# SMARC_Pinout-1.net
KiCad netlist of a schematic drawn in Altium Designer
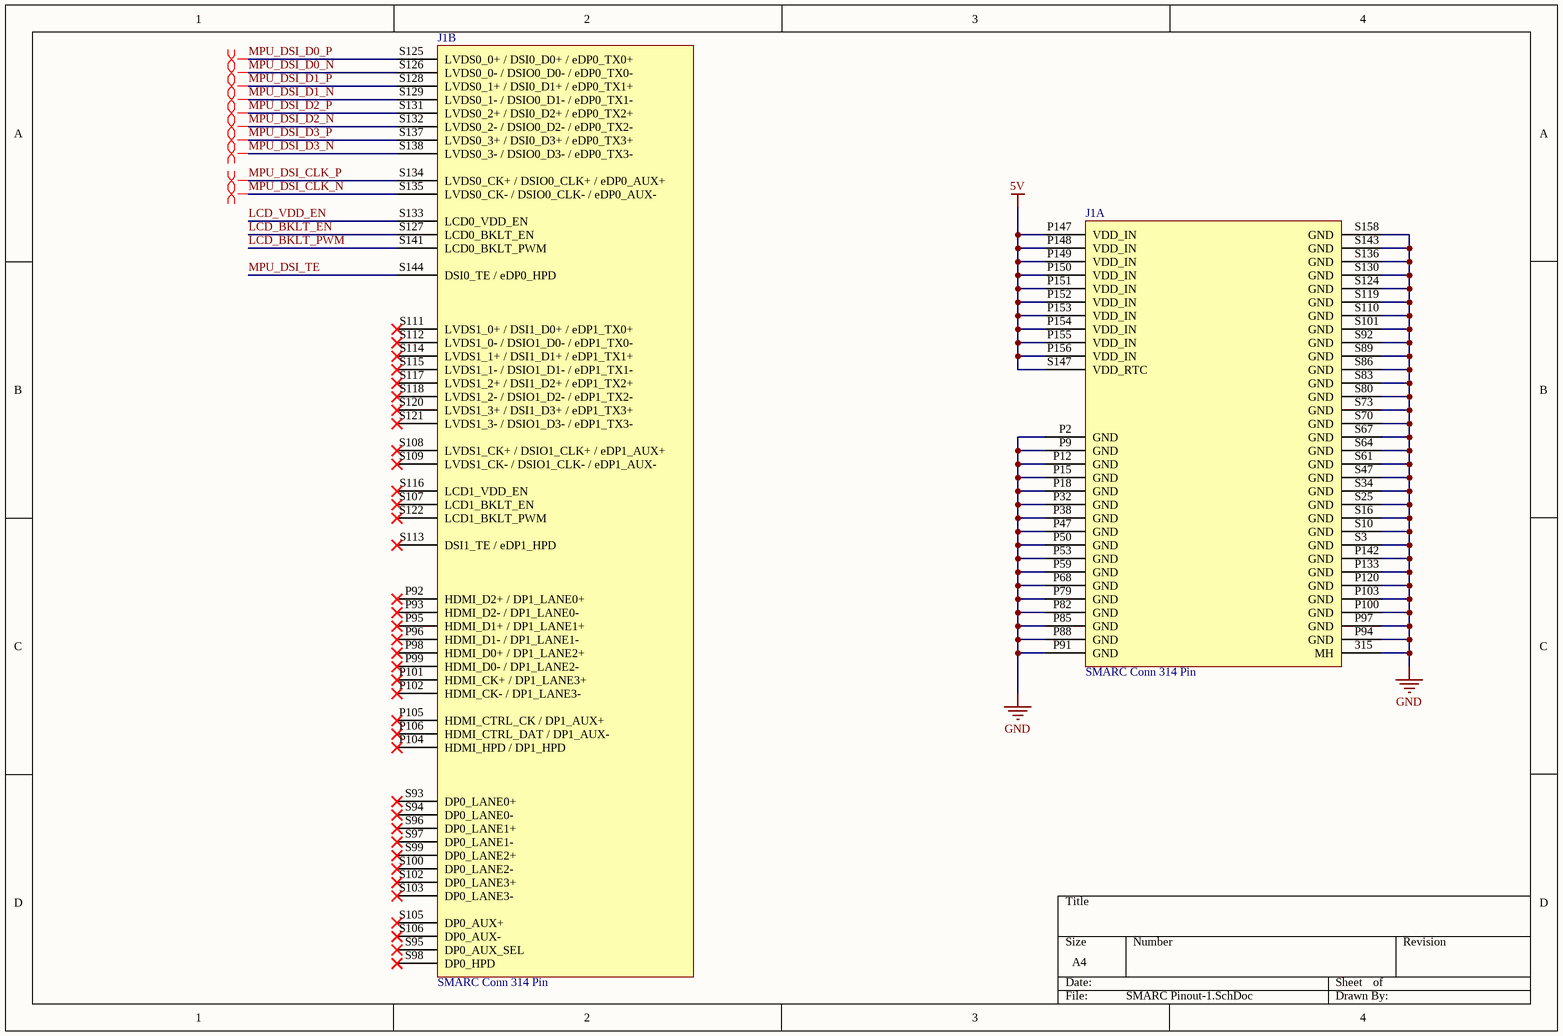
[diagram p0: SMARC Pinout-1.SchDoc]

(export (version "E")
  (design (tool "Eeschema 10.0.6"))
  (components
    (comp (ref "J1")
      (value "SMARC Conn 314 Pin")
      (footprint "SMARC Conn 314 Pin")
      (libsource (lib "Master") (part "SMARC Conn 314 Pin"))
    )
  )
  (nets
    (net (code "1") (name "/LCD_BKLT_EN") (class "Default")
      (node (ref "J1") (pin "S127") (pinfunction "LCD0_BKLT_EN_S127") (pintype "passive"))
    )
    (net (code "2") (name "/LCD_BKLT_PWM") (class "Default")
      (node (ref "J1") (pin "S141") (pinfunction "LCD0_BKLT_PWM_S141") (pintype "passive"))
    )
    (net (code "3") (name "/LCD_VDD_EN") (class "Default")
      (node (ref "J1") (pin "S133") (pinfunction "LCD0_VDD_EN_S133") (pintype "passive"))
    )
    (net (code "4") (name "/MPU_DSI_CLK_N") (class "Default")
      (node (ref "J1") (pin "S135") (pinfunction "LVDS0_CK-_/_DSIO0_CLK-_/_eDP0_AUX-_S135") (pintype "passive"))
    )
    (net (code "5") (name "/MPU_DSI_CLK_P") (class "Default")
      (node (ref "J1") (pin "S134") (pinfunction "LVDS0_CK+_/_DSIO0_CLK+_/_eDP0_AUX+_S134") (pintype "passive"))
    )
    (net (code "6") (name "/MPU_DSI_D0_N") (class "Default")
      (node (ref "J1") (pin "S126") (pinfunction "LVDS0_0-_/_DSIO0_D0-_/_eDP0_TX0-_S126") (pintype "passive"))
    )
    (net (code "7") (name "/MPU_DSI_D0_P") (class "Default")
      (node (ref "J1") (pin "S125") (pinfunction "LVDS0_0+_/_DSI0_D0+_/_eDP0_TX0+_S125") (pintype "passive"))
    )
    (net (code "8") (name "/MPU_DSI_D1_N") (class "Default")
      (node (ref "J1") (pin "S129") (pinfunction "LVDS0_1-_/_DSIO0_D1-_/_eDP0_TX1-_S129") (pintype "passive"))
    )
    (net (code "9") (name "/MPU_DSI_D1_P") (class "Default")
      (node (ref "J1") (pin "S128") (pinfunction "LVDS0_1+_/_DSI0_D1+_/_eDP0_TX1+_S128") (pintype "passive"))
    )
    (net (code "10") (name "/MPU_DSI_D2_N") (class "Default")
      (node (ref "J1") (pin "S132") (pinfunction "LVDS0_2-_/_DSIO0_D2-_/_eDP0_TX2-_S132") (pintype "passive"))
    )
    (net (code "11") (name "/MPU_DSI_D2_P") (class "Default")
      (node (ref "J1") (pin "S131") (pinfunction "LVDS0_2+_/_DSI0_D2+_/_eDP0_TX2+_S131") (pintype "passive"))
    )
    (net (code "12") (name "/MPU_DSI_D3_N") (class "Default")
      (node (ref "J1") (pin "S138") (pinfunction "LVDS0_3-_/_DSIO0_D3-_/_eDP0_TX3-_S138") (pintype "passive"))
    )
    (net (code "13") (name "/MPU_DSI_D3_P") (class "Default")
      (node (ref "J1") (pin "S137") (pinfunction "LVDS0_3+_/_DSI0_D3+_/_eDP0_TX3+_S137") (pintype "passive"))
    )
    (net (code "14") (name "/MPU_DSI_TE") (class "Default")
      (node (ref "J1") (pin "S144") (pinfunction "DSI0_TE_/_eDP0_HPD_S144") (pintype "passive"))
    )
    (net (code "15") (name "5V") (class "Default")
      (node (ref "J1") (pin "P147") (pinfunction "VDD_IN_P147") (pintype "passive"))
      (node (ref "J1") (pin "P148") (pinfunction "VDD_IN_P148") (pintype "passive"))
      (node (ref "J1") (pin "P149") (pinfunction "VDD_IN_P149") (pintype "passive"))
      (node (ref "J1") (pin "P150") (pinfunction "VDD_IN_P150") (pintype "passive"))
      (node (ref "J1") (pin "P151") (pinfunction "VDD_IN_P151") (pintype "passive"))
      (node (ref "J1") (pin "P152") (pinfunction "VDD_IN_P152") (pintype "passive"))
      (node (ref "J1") (pin "P153") (pinfunction "VDD_IN_P153") (pintype "passive"))
      (node (ref "J1") (pin "P154") (pinfunction "VDD_IN_P154") (pintype "passive"))
      (node (ref "J1") (pin "P155") (pinfunction "VDD_IN_P155") (pintype "passive"))
      (node (ref "J1") (pin "P156") (pinfunction "VDD_IN_P156") (pintype "passive"))
      (node (ref "J1") (pin "S147") (pinfunction "VDD_RTC_S147") (pintype "passive"))
    )
    (net (code "16") (name "GND") (class "Default")
      (node (ref "J1") (pin "315") (pinfunction "MH_315") (pintype "passive"))
      (node (ref "J1") (pin "P100") (pinfunction "GND_P100") (pintype "passive"))
      (node (ref "J1") (pin "P103") (pinfunction "GND_P103") (pintype "passive"))
      (node (ref "J1") (pin "P12") (pinfunction "GND_P12") (pintype "passive"))
      (node (ref "J1") (pin "P120") (pinfunction "GND_P120") (pintype "passive"))
      (node (ref "J1") (pin "P133") (pinfunction "GND_P133") (pintype "passive"))
      (node (ref "J1") (pin "P142") (pinfunction "GND_P142") (pintype "passive"))
      (node (ref "J1") (pin "P15") (pinfunction "GND_P15") (pintype "passive"))
      (node (ref "J1") (pin "P18") (pinfunction "GND_P18") (pintype "passive"))
      (node (ref "J1") (pin "P2") (pinfunction "GND_P2") (pintype "passive"))
      (node (ref "J1") (pin "P32") (pinfunction "GND_P32") (pintype "passive"))
      (node (ref "J1") (pin "P38") (pinfunction "GND_P38") (pintype "passive"))
      (node (ref "J1") (pin "P47") (pinfunction "GND_P47") (pintype "passive"))
      (node (ref "J1") (pin "P50") (pinfunction "GND_P50") (pintype "passive"))
      (node (ref "J1") (pin "P53") (pinfunction "GND_P53") (pintype "passive"))
      (node (ref "J1") (pin "P59") (pinfunction "GND_P59") (pintype "passive"))
      (node (ref "J1") (pin "P68") (pinfunction "GND_P68") (pintype "passive"))
      (node (ref "J1") (pin "P79") (pinfunction "GND_P79") (pintype "passive"))
      (node (ref "J1") (pin "P82") (pinfunction "GND_P82") (pintype "passive"))
      (node (ref "J1") (pin "P85") (pinfunction "GND_P85") (pintype "passive"))
      (node (ref "J1") (pin "P88") (pinfunction "GND_P88") (pintype "passive"))
      (node (ref "J1") (pin "P9") (pinfunction "GND_P9") (pintype "passive"))
      (node (ref "J1") (pin "P91") (pinfunction "GND_P91") (pintype "passive"))
      (node (ref "J1") (pin "P94") (pinfunction "GND_P94") (pintype "passive"))
      (node (ref "J1") (pin "P97") (pinfunction "GND_P97") (pintype "passive"))
      (node (ref "J1") (pin "S10") (pinfunction "GND_S10") (pintype "passive"))
      (node (ref "J1") (pin "S101") (pinfunction "GND_S101") (pintype "passive"))
      (node (ref "J1") (pin "S110") (pinfunction "GND_S110") (pintype "passive"))
      (node (ref "J1") (pin "S119") (pinfunction "GND_S119") (pintype "passive"))
      (node (ref "J1") (pin "S124") (pinfunction "GND_S124") (pintype "passive"))
      (node (ref "J1") (pin "S130") (pinfunction "GND_S130") (pintype "passive"))
      (node (ref "J1") (pin "S136") (pinfunction "GND_S136") (pintype "passive"))
      (node (ref "J1") (pin "S143") (pinfunction "GND_S143") (pintype "passive"))
      (node (ref "J1") (pin "S158") (pinfunction "GND_S158") (pintype "passive"))
      (node (ref "J1") (pin "S16") (pinfunction "GND_S16") (pintype "passive"))
      (node (ref "J1") (pin "S25") (pinfunction "GND_S25") (pintype "passive"))
      (node (ref "J1") (pin "S3") (pinfunction "GND_S3") (pintype "passive"))
      (node (ref "J1") (pin "S34") (pinfunction "GND_S34") (pintype "passive"))
      (node (ref "J1") (pin "S47") (pinfunction "GND_S47") (pintype "passive"))
      (node (ref "J1") (pin "S61") (pinfunction "GND_S61") (pintype "passive"))
      (node (ref "J1") (pin "S64") (pinfunction "GND_S64") (pintype "passive"))
      (node (ref "J1") (pin "S67") (pinfunction "GND_S67") (pintype "passive"))
      (node (ref "J1") (pin "S70") (pinfunction "GND_S70") (pintype "passive"))
      (node (ref "J1") (pin "S73") (pinfunction "GND_S73") (pintype "passive"))
      (node (ref "J1") (pin "S80") (pinfunction "GND_S80") (pintype "passive"))
      (node (ref "J1") (pin "S83") (pinfunction "GND_S83") (pintype "passive"))
      (node (ref "J1") (pin "S86") (pinfunction "GND_S86") (pintype "passive"))
      (node (ref "J1") (pin "S89") (pinfunction "GND_S89") (pintype "passive"))
      (node (ref "J1") (pin "S92") (pinfunction "GND_S92") (pintype "passive"))
    )
    (net (code "17") (name "unconnected-(J1B-DP0_AUX+-PadS105)") (class "Default")
      (node (ref "J1") (pin "S105") (pinfunction "DP0_AUX+_S105") (pintype "passive+no_connect"))
    )
    (net (code "18") (name "unconnected-(J1B-DP0_AUX--PadS106)") (class "Default")
      (node (ref "J1") (pin "S106") (pinfunction "DP0_AUX-_S106") (pintype "passive+no_connect"))
    )
    (net (code "19") (name "unconnected-(J1B-DP0_AUX_SEL-PadS95)") (class "Default")
      (node (ref "J1") (pin "S95") (pinfunction "DP0_AUX_SEL_S95") (pintype "passive+no_connect"))
    )
    (net (code "20") (name "unconnected-(J1B-DP0_HPD-PadS98)") (class "Default")
      (node (ref "J1") (pin "S98") (pinfunction "DP0_HPD_S98") (pintype "passive+no_connect"))
    )
    (net (code "21") (name "unconnected-(J1B-DP0_LANE0+-PadS93)") (class "Default")
      (node (ref "J1") (pin "S93") (pinfunction "DP0_LANE0+_S93") (pintype "passive+no_connect"))
    )
    (net (code "22") (name "unconnected-(J1B-DP0_LANE0--PadS94)") (class "Default")
      (node (ref "J1") (pin "S94") (pinfunction "DP0_LANE0-_S94") (pintype "passive+no_connect"))
    )
    (net (code "23") (name "unconnected-(J1B-DP0_LANE1+-PadS96)") (class "Default")
      (node (ref "J1") (pin "S96") (pinfunction "DP0_LANE1+_S96") (pintype "passive+no_connect"))
    )
    (net (code "24") (name "unconnected-(J1B-DP0_LANE1--PadS97)") (class "Default")
      (node (ref "J1") (pin "S97") (pinfunction "DP0_LANE1-_S97") (pintype "passive+no_connect"))
    )
    (net (code "25") (name "unconnected-(J1B-DP0_LANE2+-PadS99)") (class "Default")
      (node (ref "J1") (pin "S99") (pinfunction "DP0_LANE2+_S99") (pintype "passive+no_connect"))
    )
    (net (code "26") (name "unconnected-(J1B-DP0_LANE2--PadS100)") (class "Default")
      (node (ref "J1") (pin "S100") (pinfunction "DP0_LANE2-_S100") (pintype "passive+no_connect"))
    )
    (net (code "27") (name "unconnected-(J1B-DP0_LANE3+-PadS102)") (class "Default")
      (node (ref "J1") (pin "S102") (pinfunction "DP0_LANE3+_S102") (pintype "passive+no_connect"))
    )
    (net (code "28") (name "unconnected-(J1B-DP0_LANE3--PadS103)") (class "Default")
      (node (ref "J1") (pin "S103") (pinfunction "DP0_LANE3-_S103") (pintype "passive+no_connect"))
    )
    (net (code "29") (name "unconnected-(J1B-DSI1_TE_{slash}_eDP1_HPD-PadS113)") (class "Default")
      (node (ref "J1") (pin "S113") (pinfunction "DSI1_TE_/_eDP1_HPD_S113") (pintype "passive+no_connect"))
    )
    (net (code "30") (name "unconnected-(J1B-HDMI_CK+_{slash}_DP1_LANE3+-PadP101)") (class "Default")
      (node (ref "J1") (pin "P101") (pinfunction "HDMI_CK+_/_DP1_LANE3+_P101") (pintype "passive+no_connect"))
    )
    (net (code "31") (name "unconnected-(J1B-HDMI_CK-_{slash}_DP1_LANE3--PadP102)") (class "Default")
      (node (ref "J1") (pin "P102") (pinfunction "HDMI_CK-_/_DP1_LANE3-_P102") (pintype "passive+no_connect"))
    )
    (net (code "32") (name "unconnected-(J1B-HDMI_CTRL_CK_{slash}_DP1_AUX+-PadP105)") (class "Default")
      (node (ref "J1") (pin "P105") (pinfunction "HDMI_CTRL_CK_/_DP1_AUX+_P105") (pintype "passive+no_connect"))
    )
    (net (code "33") (name "unconnected-(J1B-HDMI_CTRL_DAT_{slash}_DP1_AUX--PadP106)") (class "Default")
      (node (ref "J1") (pin "P106") (pinfunction "HDMI_CTRL_DAT_/_DP1_AUX-_P106") (pintype "passive+no_connect"))
    )
    (net (code "34") (name "unconnected-(J1B-HDMI_D0+_{slash}_DP1_LANE2+-PadP98)") (class "Default")
      (node (ref "J1") (pin "P98") (pinfunction "HDMI_D0+_/_DP1_LANE2+_P98") (pintype "passive+no_connect"))
    )
    (net (code "35") (name "unconnected-(J1B-HDMI_D0-_{slash}_DP1_LANE2--PadP99)") (class "Default")
      (node (ref "J1") (pin "P99") (pinfunction "HDMI_D0-_/_DP1_LANE2-_P99") (pintype "passive+no_connect"))
    )
    (net (code "36") (name "unconnected-(J1B-HDMI_D1+_{slash}_DP1_LANE1+-PadP95)") (class "Default")
      (node (ref "J1") (pin "P95") (pinfunction "HDMI_D1+_/_DP1_LANE1+_P95") (pintype "passive+no_connect"))
    )
    (net (code "37") (name "unconnected-(J1B-HDMI_D1-_{slash}_DP1_LANE1--PadP96)") (class "Default")
      (node (ref "J1") (pin "P96") (pinfunction "HDMI_D1-_/_DP1_LANE1-_P96") (pintype "passive+no_connect"))
    )
    (net (code "38") (name "unconnected-(J1B-HDMI_D2+_{slash}_DP1_LANE0+-PadP92)") (class "Default")
      (node (ref "J1") (pin "P92") (pinfunction "HDMI_D2+_/_DP1_LANE0+_P92") (pintype "passive+no_connect"))
    )
    (net (code "39") (name "unconnected-(J1B-HDMI_D2-_{slash}_DP1_LANE0--PadP93)") (class "Default")
      (node (ref "J1") (pin "P93") (pinfunction "HDMI_D2-_/_DP1_LANE0-_P93") (pintype "passive+no_connect"))
    )
    (net (code "40") (name "unconnected-(J1B-HDMI_HPD_{slash}_DP1_HPD-PadP104)") (class "Default")
      (node (ref "J1") (pin "P104") (pinfunction "HDMI_HPD_/_DP1_HPD_P104") (pintype "passive+no_connect"))
    )
    (net (code "41") (name "unconnected-(J1B-LCD1_BKLT_EN-PadS107)") (class "Default")
      (node (ref "J1") (pin "S107") (pinfunction "LCD1_BKLT_EN_S107") (pintype "passive+no_connect"))
    )
    (net (code "42") (name "unconnected-(J1B-LCD1_BKLT_PWM-PadS122)") (class "Default")
      (node (ref "J1") (pin "S122") (pinfunction "LCD1_BKLT_PWM_S122") (pintype "passive+no_connect"))
    )
    (net (code "43") (name "unconnected-(J1B-LCD1_VDD_EN-PadS116)") (class "Default")
      (node (ref "J1") (pin "S116") (pinfunction "LCD1_VDD_EN_S116") (pintype "passive+no_connect"))
    )
    (net (code "44") (name "unconnected-(J1B-LVDS1_0+_{slash}_DSI1_D0+_{slash}_eDP1_TX0+-PadS111)") (class "Default")
      (node (ref "J1") (pin "S111") (pinfunction "LVDS1_0+_/_DSI1_D0+_/_eDP1_TX0+_S111") (pintype "passive+no_connect"))
    )
    (net (code "45") (name "unconnected-(J1B-LVDS1_0-_{slash}_DSIO1_D0-_{slash}_eDP1_TX0--PadS112)") (class "Default")
      (node (ref "J1") (pin "S112") (pinfunction "LVDS1_0-_/_DSIO1_D0-_/_eDP1_TX0-_S112") (pintype "passive+no_connect"))
    )
    (net (code "46") (name "unconnected-(J1B-LVDS1_1+_{slash}_DSI1_D1+_{slash}_eDP1_TX1+-PadS114)") (class "Default")
      (node (ref "J1") (pin "S114") (pinfunction "LVDS1_1+_/_DSI1_D1+_/_eDP1_TX1+_S114") (pintype "passive+no_connect"))
    )
    (net (code "47") (name "unconnected-(J1B-LVDS1_1-_{slash}_DSIO1_D1-_{slash}_eDP1_TX1--PadS115)") (class "Default")
      (node (ref "J1") (pin "S115") (pinfunction "LVDS1_1-_/_DSIO1_D1-_/_eDP1_TX1-_S115") (pintype "passive+no_connect"))
    )
    (net (code "48") (name "unconnected-(J1B-LVDS1_2+_{slash}_DSI1_D2+_{slash}_eDP1_TX2+-PadS117)") (class "Default")
      (node (ref "J1") (pin "S117") (pinfunction "LVDS1_2+_/_DSI1_D2+_/_eDP1_TX2+_S117") (pintype "passive+no_connect"))
    )
    (net (code "49") (name "unconnected-(J1B-LVDS1_2-_{slash}_DSIO1_D2-_{slash}_eDP1_TX2--PadS118)") (class "Default")
      (node (ref "J1") (pin "S118") (pinfunction "LVDS1_2-_/_DSIO1_D2-_/_eDP1_TX2-_S118") (pintype "passive+no_connect"))
    )
    (net (code "50") (name "unconnected-(J1B-LVDS1_3+_{slash}_DSI1_D3+_{slash}_eDP1_TX3+-PadS120)") (class "Default")
      (node (ref "J1") (pin "S120") (pinfunction "LVDS1_3+_/_DSI1_D3+_/_eDP1_TX3+_S120") (pintype "passive+no_connect"))
    )
    (net (code "51") (name "unconnected-(J1B-LVDS1_3-_{slash}_DSIO1_D3-_{slash}_eDP1_TX3--PadS121)") (class "Default")
      (node (ref "J1") (pin "S121") (pinfunction "LVDS1_3-_/_DSIO1_D3-_/_eDP1_TX3-_S121") (pintype "passive+no_connect"))
    )
    (net (code "52") (name "unconnected-(J1B-LVDS1_CK+_{slash}_DSIO1_CLK+_{slash}_eDP1_AUX+-PadS108)") (class "Default")
      (node (ref "J1") (pin "S108") (pinfunction "LVDS1_CK+_/_DSIO1_CLK+_/_eDP1_AUX+_S108") (pintype "passive+no_connect"))
    )
    (net (code "53") (name "unconnected-(J1B-LVDS1_CK-_{slash}_DSIO1_CLK-_{slash}_eDP1_AUX--PadS109)") (class "Default")
      (node (ref "J1") (pin "S109") (pinfunction "LVDS1_CK-_/_DSIO1_CLK-_/_eDP1_AUX-_S109") (pintype "passive+no_connect"))
    )
  )
)
